# EasyEdaScheme.net
KiCad netlist of a schematic drawn in EasyEDA
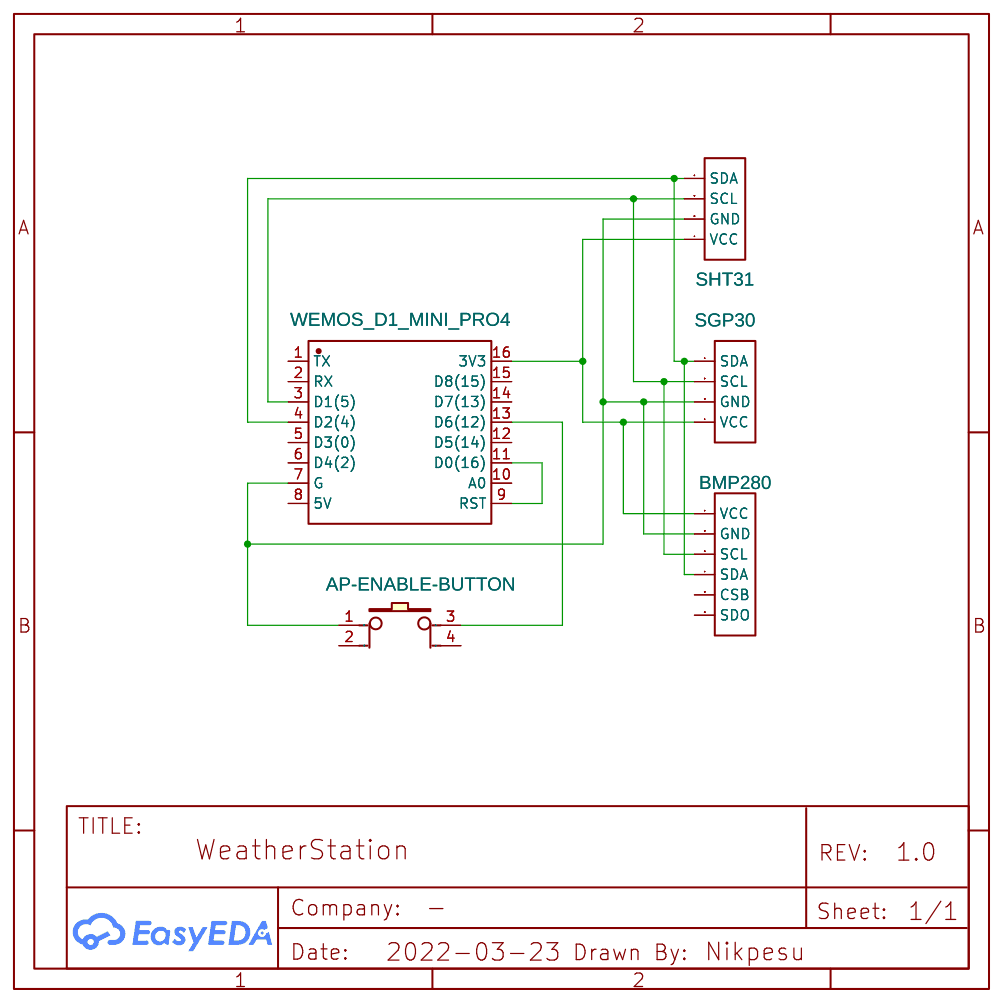
[diagram p0: schematic sheet]

(export (version "E")
  (design (tool "Eeschema 10.0.6"))
  (components
    (comp (ref "AP-ENABLE-BUTTON")
      (value "button6*6*8.5")
      (fields (field (name "BOM_Supplier Part") "C59980"))
      (libsource (lib "") (part "button6*6*8.5"))
    )
    (comp (ref "BMP280")
      (value "HDR-F-2.54_1x6")
      (fields (field (name "BOM_Supplier Part") "C40877"))
      (libsource (lib "") (part "HDR-F-2.54_1x6"))
    )
    (comp (ref "SGP30")
      (value "HDR-F-2.54_1x4")
      (fields (field (name "BOM_Supplier Part") "C225501"))
      (libsource (lib "") (part "HDR-F-2.54_1x4_1"))
    )
    (comp (ref "SHT31")
      (value "HDR-F-2.54_1x4")
      (fields (field (name "BOM_Supplier Part") "C225501"))
      (libsource (lib "") (part "HDR-F-2.54_1x4"))
    )
    (comp (ref "U1")
      (value "WEMOS_D1_MINI_PRO4")
      (fields
        (field (name "BOM_Manufacturer Part") "Wemos_D1_mini_Pro4")
        (field (name "BOM_Supplier Part") "C2837266")
      )
      (libsource (lib "") (part "WEMOS_D1_MINI_PRO4"))
    )
  )
  (nets
    (net (code "1") (name "Net-(BMP280-GND)") (class "Default")
      (node (ref "AP-ENABLE-BUTTON") (pin "1") (pinfunction "1_1") (pintype "input"))
      (node (ref "BMP280") (pin "2") (pinfunction "GND_2") (pintype "input"))
      (node (ref "SGP30") (pin "3") (pinfunction "GND_3") (pintype "unspecified"))
      (node (ref "SHT31") (pin "3") (pinfunction "GND_3") (pintype "unspecified"))
      (node (ref "U1") (pin "7") (pinfunction "G_7") (pintype "unspecified"))
    )
    (net (code "2") (name "Net-(BMP280-SCL)") (class "Default")
      (node (ref "BMP280") (pin "3") (pinfunction "SCL_3") (pintype "input"))
      (node (ref "SGP30") (pin "2") (pinfunction "SCL_2") (pintype "unspecified"))
      (node (ref "SHT31") (pin "2") (pinfunction "SCL_2") (pintype "unspecified"))
      (node (ref "U1") (pin "3") (pinfunction "D1(5)_3") (pintype "unspecified"))
    )
    (net (code "3") (name "Net-(BMP280-SDA)") (class "Default")
      (node (ref "BMP280") (pin "4") (pinfunction "SDA_4") (pintype "input"))
      (node (ref "SGP30") (pin "1") (pinfunction "SDA_1") (pintype "unspecified"))
      (node (ref "SHT31") (pin "1") (pinfunction "SDA_1") (pintype "unspecified"))
      (node (ref "U1") (pin "4") (pinfunction "D2(4)_4") (pintype "unspecified"))
    )
    (net (code "4") (name "Net-(BMP280-VCC)") (class "Default")
      (node (ref "BMP280") (pin "1") (pinfunction "VCC_1") (pintype "input"))
      (node (ref "SGP30") (pin "4") (pinfunction "VCC_4") (pintype "unspecified"))
      (node (ref "SHT31") (pin "4") (pinfunction "VCC_4") (pintype "unspecified"))
      (node (ref "U1") (pin "16") (pinfunction "3V3_16") (pintype "unspecified"))
    )
    (net (code "5") (name "Net-(U1-D0(16))") (class "Default")
      (node (ref "U1") (pin "11") (pinfunction "D0(16)_11") (pintype "unspecified"))
      (node (ref "U1") (pin "9") (pinfunction "RST_9") (pintype "unspecified"))
    )
    (net (code "6") (name "Net-(U1-D6(12))") (class "Default")
      (node (ref "AP-ENABLE-BUTTON") (pin "3") (pinfunction "3_3") (pintype "input"))
      (node (ref "U1") (pin "13") (pinfunction "D6(12)_13") (pintype "unspecified"))
    )
    (net (code "7") (name "unconnected-(AP-ENABLE-BUTTON-Pad2)") (class "Default")
      (node (ref "AP-ENABLE-BUTTON") (pin "2") (pinfunction "2_2") (pintype "input"))
    )
    (net (code "8") (name "unconnected-(AP-ENABLE-BUTTON-Pad4)") (class "Default")
      (node (ref "AP-ENABLE-BUTTON") (pin "4") (pinfunction "4_4") (pintype "input"))
    )
    (net (code "9") (name "unconnected-(BMP280-CSB-Pad5)") (class "Default")
      (node (ref "BMP280") (pin "5") (pinfunction "CSB_5") (pintype "input"))
    )
    (net (code "10") (name "unconnected-(BMP280-SDO-Pad6)") (class "Default")
      (node (ref "BMP280") (pin "6") (pinfunction "SDO_6") (pintype "input"))
    )
    (net (code "11") (name "unconnected-(U1-5V-Pad8)") (class "Default")
      (node (ref "U1") (pin "8") (pinfunction "5V_8") (pintype "unspecified"))
    )
    (net (code "12") (name "unconnected-(U1-A0-Pad10)") (class "Default")
      (node (ref "U1") (pin "10") (pinfunction "A0_10") (pintype "unspecified"))
    )
    (net (code "13") (name "unconnected-(U1-D3(0)-Pad5)") (class "Default")
      (node (ref "U1") (pin "5") (pinfunction "D3(0)_5") (pintype "unspecified"))
    )
    (net (code "14") (name "unconnected-(U1-D4(2)-Pad6)") (class "Default")
      (node (ref "U1") (pin "6") (pinfunction "D4(2)_6") (pintype "unspecified"))
    )
    (net (code "15") (name "unconnected-(U1-D5(14)-Pad12)") (class "Default")
      (node (ref "U1") (pin "12") (pinfunction "D5(14)_12") (pintype "unspecified"))
    )
    (net (code "16") (name "unconnected-(U1-D7(13)-Pad14)") (class "Default")
      (node (ref "U1") (pin "14") (pinfunction "D7(13)_14") (pintype "unspecified"))
    )
    (net (code "17") (name "unconnected-(U1-D8(15)-Pad15)") (class "Default")
      (node (ref "U1") (pin "15") (pinfunction "D8(15)_15") (pintype "unspecified"))
    )
    (net (code "18") (name "unconnected-(U1-RX-Pad2)") (class "Default")
      (node (ref "U1") (pin "2") (pinfunction "RX_2") (pintype "unspecified"))
    )
    (net (code "19") (name "unconnected-(U1-TX-Pad1)") (class "Default")
      (node (ref "U1") (pin "1") (pinfunction "TX_1") (pintype "unspecified"))
    )
  )
)
